# mainboard.net
KiCad netlist of a schematic drawn in EAGLE
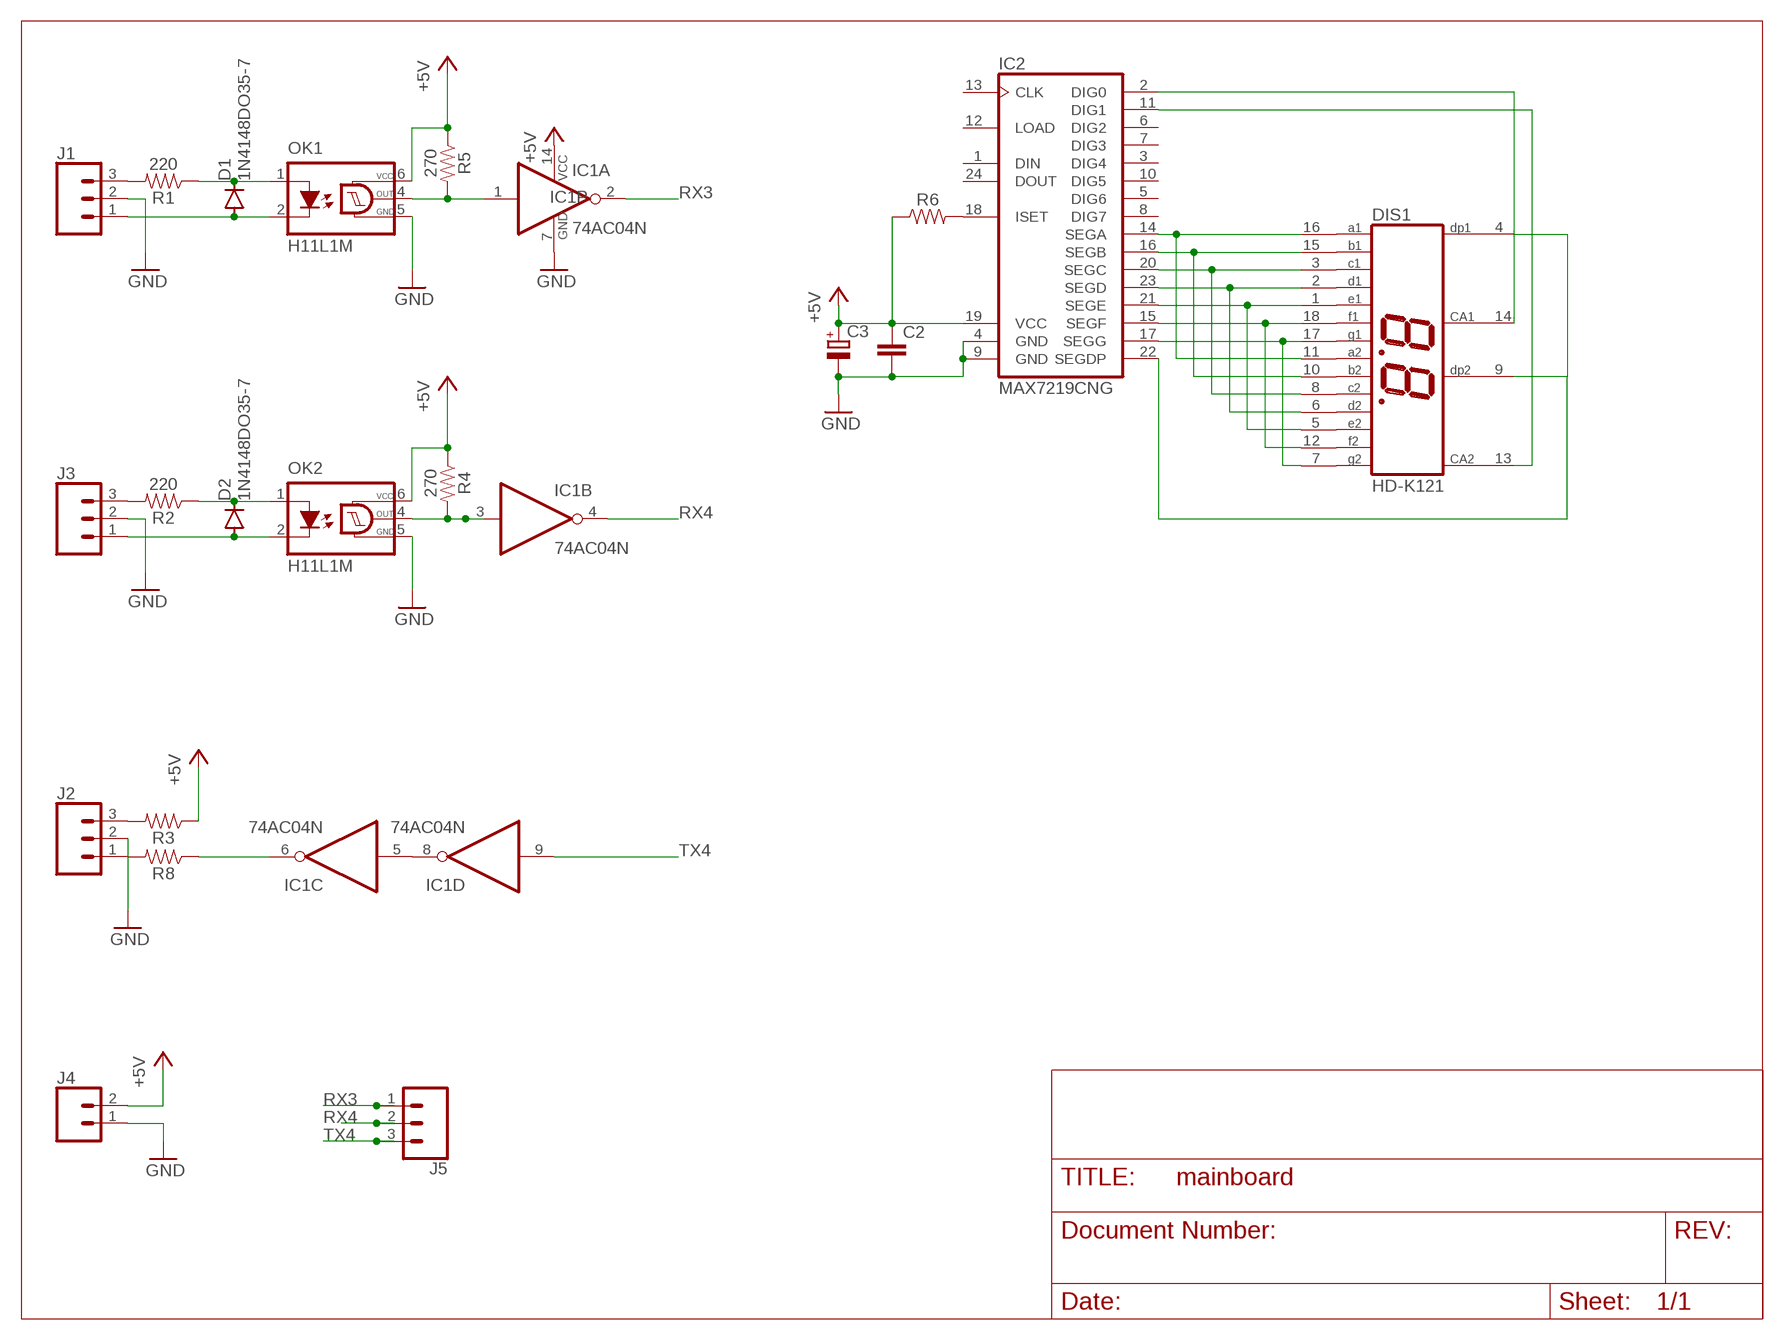
[diagram p0: schematic, sheet 1]

(export (version "E")
  (design (tool "Eeschema 10.0.6"))
  (components
    (comp (ref "C2")
      (value "C-EU025-025X050")
      (footprint "eagle-import:C025-025X050")
      (libsource (lib "eagle-import") (part "C-EU025-025X050"))
    )
    (comp (ref "C3")
      (value "CPOL-EUE1.8-4")
      (footprint "eagle-import:E1,8-4")
      (libsource (lib "eagle-import") (part "CPOL-EUE1.8-4"))
    )
    (comp (ref "D1")
      (value "1N4148DO35-7")
      (footprint "eagle-import:DO35-7")
      (libsource (lib "eagle-import") (part "1N4148DO35-7"))
    )
    (comp (ref "D2")
      (value "1N4148DO35-7")
      (footprint "eagle-import:DO35-7")
      (libsource (lib "eagle-import") (part "1N4148DO35-7"))
    )
    (comp (ref "DIS1")
      (value "HD-K121")
      (footprint "eagle-import:HDSP-R")
      (libsource (lib "eagle-import") (part "HD-K121"))
    )
    (comp (ref "IC1")
      (value "74AC04N")
      (footprint "eagle-import:DIL14")
      (libsource (lib "eagle-import") (part "7404NAC"))
    )
    (comp (ref "IC2")
      (value "MAX7219CNG")
      (footprint "eagle-import:DIL24-3")
      (fields (field (name "MF") "MAXIM"))
      (libsource (lib "eagle-import") (part "MAX7219CNG"))
    )
    (comp (ref "J1")
      (value "CONN_03")
      (footprint "eagle-import:1X03")
      (libsource (lib "eagle-import") (part "CONN_03"))
    )
    (comp (ref "J2")
      (value "CONN_03")
      (footprint "eagle-import:1X03")
      (libsource (lib "eagle-import") (part "CONN_03"))
    )
    (comp (ref "J3")
      (value "CONN_03")
      (footprint "eagle-import:1X03")
      (libsource (lib "eagle-import") (part "CONN_03"))
    )
    (comp (ref "J4")
      (value "CONN_02")
      (footprint "eagle-import:1X02")
      (libsource (lib "eagle-import") (part "CONN_02"))
    )
    (comp (ref "J5")
      (value "CONN_03")
      (footprint "eagle-import:1X03")
      (libsource (lib "eagle-import") (part "CONN_03"))
    )
    (comp (ref "OK1")
      (value "H11L1M")
      (footprint "eagle-import:DIL06")
      (fields (field (name "MF") "FAIRCHILD SEMICONDUCTOR") (field (name "MPN") "H11L1-M"))
      (libsource (lib "eagle-import") (part "H11LM1"))
    )
    (comp (ref "OK2")
      (value "H11L1M")
      (footprint "eagle-import:DIL06")
      (fields (field (name "MF") "FAIRCHILD SEMICONDUCTOR") (field (name "MPN") "H11L1-M"))
      (libsource (lib "eagle-import") (part "H11LM1"))
    )
    (comp (ref "R1")
      (value "220")
      (footprint "eagle-import:AXIAL-0.3")
      (libsource (lib "eagle-import") (part "RESISTORAXIAL-0.3"))
    )
    (comp (ref "R2")
      (value "220")
      (footprint "eagle-import:AXIAL-0.3")
      (libsource (lib "eagle-import") (part "RESISTORAXIAL-0.3"))
    )
    (comp (ref "R3")
      (value "RESISTORAXIAL-0.3")
      (footprint "eagle-import:AXIAL-0.3")
      (libsource (lib "eagle-import") (part "RESISTORAXIAL-0.3"))
    )
    (comp (ref "R4")
      (value "270")
      (footprint "eagle-import:AXIAL-0.3")
      (libsource (lib "eagle-import") (part "RESISTORAXIAL-0.3"))
    )
    (comp (ref "R5")
      (value "270")
      (footprint "eagle-import:AXIAL-0.3")
      (libsource (lib "eagle-import") (part "RESISTORAXIAL-0.3"))
    )
    (comp (ref "R6")
      (value "RESISTORAXIAL-0.3")
      (footprint "eagle-import:AXIAL-0.3")
      (libsource (lib "eagle-import") (part "RESISTORAXIAL-0.3"))
    )
    (comp (ref "R8")
      (value "RESISTORAXIAL-0.3")
      (footprint "eagle-import:AXIAL-0.3")
      (libsource (lib "eagle-import") (part "RESISTORAXIAL-0.3"))
    )
  )
  (nets
    (net (code "1") (name "+5V") (class "Default")
      (node (ref "C2") (pin "1") (pinfunction "1_1") (pintype "passive"))
      (node (ref "C3") (pin "+") (pinfunction "+_+") (pintype "passive"))
      (node (ref "IC1") (pin "14") (pinfunction "VCC_14") (pintype "power_in"))
      (node (ref "IC2") (pin "19") (pinfunction "VCC_19") (pintype "power_in"))
      (node (ref "J4") (pin "2") (pinfunction "2_2") (pintype "passive"))
      (node (ref "OK1") (pin "6") (pinfunction "VCC_6") (pintype "power_in"))
      (node (ref "OK2") (pin "6") (pinfunction "VCC_6") (pintype "power_in"))
      (node (ref "R3") (pin "P$1") (pinfunction "1_P$1") (pintype "passive"))
      (node (ref "R4") (pin "P$1") (pinfunction "1_P$1") (pintype "passive"))
      (node (ref "R5") (pin "P$1") (pinfunction "1_P$1") (pintype "passive"))
      (node (ref "R6") (pin "P$1") (pinfunction "1_P$1") (pintype "passive"))
    )
    (net (code "2") (name "/RX3") (class "Default")
      (node (ref "IC1") (pin "2") (pinfunction "O_2") (pintype "output"))
      (node (ref "J5") (pin "1") (pinfunction "1_1") (pintype "passive"))
    )
    (net (code "3") (name "/RX4") (class "Default")
      (node (ref "IC1") (pin "4") (pinfunction "O_4") (pintype "output"))
      (node (ref "J5") (pin "2") (pinfunction "2_2") (pintype "passive"))
    )
    (net (code "4") (name "/TX4") (class "Default")
      (node (ref "IC1") (pin "9") (pinfunction "I_9") (pintype "input"))
      (node (ref "J5") (pin "3") (pinfunction "3_3") (pintype "passive"))
    )
    (net (code "5") (name "GND") (class "Default")
      (node (ref "C2") (pin "2") (pinfunction "2_2") (pintype "passive"))
      (node (ref "C3") (pin "-") (pinfunction "-_-") (pintype "passive"))
      (node (ref "IC1") (pin "7") (pinfunction "GND_7") (pintype "power_in"))
      (node (ref "IC2") (pin "4") (pinfunction "GND_4") (pintype "power_in"))
      (node (ref "IC2") (pin "9") (pinfunction "GND_9") (pintype "power_in"))
      (node (ref "J1") (pin "2") (pinfunction "2_2") (pintype "passive"))
      (node (ref "J2") (pin "2") (pinfunction "2_2") (pintype "passive"))
      (node (ref "J3") (pin "2") (pinfunction "2_2") (pintype "passive"))
      (node (ref "J4") (pin "1") (pinfunction "1_1") (pintype "passive"))
      (node (ref "OK1") (pin "5") (pinfunction "GND_5") (pintype "power_in"))
      (node (ref "OK2") (pin "5") (pinfunction "GND_5") (pintype "power_in"))
    )
    (net (code "6") (name "Net-(DIS1-A1)") (class "Default")
      (node (ref "DIS1") (pin "11") (pinfunction "A2_11") (pintype "passive"))
      (node (ref "DIS1") (pin "16") (pinfunction "A1_16") (pintype "passive"))
      (node (ref "IC2") (pin "14") (pinfunction "SEGA_14") (pintype "output"))
    )
    (net (code "7") (name "Net-(DIS1-B1)") (class "Default")
      (node (ref "DIS1") (pin "10") (pinfunction "B2_10") (pintype "passive"))
      (node (ref "DIS1") (pin "15") (pinfunction "B1_15") (pintype "passive"))
      (node (ref "IC2") (pin "16") (pinfunction "SEGB_16") (pintype "output"))
    )
    (net (code "8") (name "Net-(DIS1-C1)") (class "Default")
      (node (ref "DIS1") (pin "3") (pinfunction "C1_3") (pintype "passive"))
      (node (ref "DIS1") (pin "8") (pinfunction "C2_8") (pintype "passive"))
      (node (ref "IC2") (pin "20") (pinfunction "SEGC_20") (pintype "output"))
    )
    (net (code "9") (name "Net-(DIS1-CA1)") (class "Default")
      (node (ref "DIS1") (pin "14") (pinfunction "CA1_14") (pintype "passive"))
      (node (ref "IC2") (pin "2") (pinfunction "DIG0_2") (pintype "output"))
    )
    (net (code "10") (name "Net-(DIS1-CA2)") (class "Default")
      (node (ref "DIS1") (pin "13") (pinfunction "CA2_13") (pintype "passive"))
      (node (ref "IC2") (pin "11") (pinfunction "DIG1_11") (pintype "output"))
    )
    (net (code "11") (name "Net-(DIS1-D1)") (class "Default")
      (node (ref "DIS1") (pin "2") (pinfunction "D1_2") (pintype "passive"))
      (node (ref "DIS1") (pin "6") (pinfunction "D2_6") (pintype "passive"))
      (node (ref "IC2") (pin "23") (pinfunction "SEGD_23") (pintype "output"))
    )
    (net (code "12") (name "Net-(DIS1-DP1)") (class "Default")
      (node (ref "DIS1") (pin "4") (pinfunction "DP1_4") (pintype "passive"))
      (node (ref "DIS1") (pin "9") (pinfunction "DP2_9") (pintype "passive"))
      (node (ref "IC2") (pin "22") (pinfunction "SEGDP_22") (pintype "output"))
    )
    (net (code "13") (name "Net-(DIS1-E1)") (class "Default")
      (node (ref "DIS1") (pin "1") (pinfunction "E1_1") (pintype "passive"))
      (node (ref "DIS1") (pin "5") (pinfunction "E2_5") (pintype "passive"))
      (node (ref "IC2") (pin "21") (pinfunction "SEGE_21") (pintype "output"))
    )
    (net (code "14") (name "Net-(DIS1-F1)") (class "Default")
      (node (ref "DIS1") (pin "12") (pinfunction "F2_12") (pintype "passive"))
      (node (ref "DIS1") (pin "18") (pinfunction "F1_18") (pintype "passive"))
      (node (ref "IC2") (pin "15") (pinfunction "SEGF_15") (pintype "output"))
    )
    (net (code "15") (name "Net-(DIS1-G1)") (class "Default")
      (node (ref "DIS1") (pin "17") (pinfunction "G1_17") (pintype "passive"))
      (node (ref "DIS1") (pin "7") (pinfunction "G2_7") (pintype "passive"))
      (node (ref "IC2") (pin "17") (pinfunction "SEGG_17") (pintype "output"))
    )
    (net (code "16") (name "Net-(IC1A-I)") (class "Default")
      (node (ref "IC1") (pin "1") (pinfunction "I_1") (pintype "input"))
      (node (ref "OK1") (pin "4") (pinfunction "OUT_4") (pintype "output"))
      (node (ref "R5") (pin "P$2") (pinfunction "2_P$2") (pintype "passive"))
    )
    (net (code "17") (name "Net-(IC1B-I)") (class "Default")
      (node (ref "IC1") (pin "3") (pinfunction "I_3") (pintype "input"))
      (node (ref "OK2") (pin "4") (pinfunction "OUT_4") (pintype "output"))
      (node (ref "R4") (pin "P$2") (pinfunction "2_P$2") (pintype "passive"))
    )
    (net (code "18") (name "Net-(IC1C-I)") (class "Default")
      (node (ref "IC1") (pin "5") (pinfunction "I_5") (pintype "input"))
      (node (ref "IC1") (pin "8") (pinfunction "O_8") (pintype "output"))
    )
    (net (code "19") (name "Net-(IC1C-O)") (class "Default")
      (node (ref "IC1") (pin "6") (pinfunction "O_6") (pintype "output"))
      (node (ref "R8") (pin "P$1") (pinfunction "1_P$1") (pintype "passive"))
    )
    (net (code "20") (name "Net-(IC2-ISET)") (class "Default")
      (node (ref "IC2") (pin "18") (pinfunction "ISET_18") (pintype "input"))
      (node (ref "R6") (pin "P$2") (pinfunction "2_P$2") (pintype "passive"))
    )
    (net (code "21") (name "Net-(OK1-A)") (class "Default")
      (node (ref "D1") (pin "C") (pinfunction "C_C") (pintype "passive"))
      (node (ref "OK1") (pin "1") (pinfunction "A_1") (pintype "passive"))
      (node (ref "R1") (pin "P$1") (pinfunction "1_P$1") (pintype "passive"))
    )
    (net (code "22") (name "Net-(OK1-C)") (class "Default")
      (node (ref "D1") (pin "A") (pinfunction "A_A") (pintype "passive"))
      (node (ref "J1") (pin "1") (pinfunction "1_1") (pintype "passive"))
      (node (ref "OK1") (pin "2") (pinfunction "C_2") (pintype "passive"))
    )
    (net (code "23") (name "Net-(OK2-A)") (class "Default")
      (node (ref "D2") (pin "C") (pinfunction "C_C") (pintype "passive"))
      (node (ref "OK2") (pin "1") (pinfunction "A_1") (pintype "passive"))
      (node (ref "R2") (pin "P$1") (pinfunction "1_P$1") (pintype "passive"))
    )
    (net (code "24") (name "Net-(OK2-C)") (class "Default")
      (node (ref "D2") (pin "A") (pinfunction "A_A") (pintype "passive"))
      (node (ref "J3") (pin "1") (pinfunction "1_1") (pintype "passive"))
      (node (ref "OK2") (pin "2") (pinfunction "C_2") (pintype "passive"))
    )
    (net (code "25") (name "Net-(R1-2)") (class "Default")
      (node (ref "J1") (pin "3") (pinfunction "3_3") (pintype "passive"))
      (node (ref "R1") (pin "P$2") (pinfunction "2_P$2") (pintype "passive"))
    )
    (net (code "26") (name "Net-(R2-2)") (class "Default")
      (node (ref "J3") (pin "3") (pinfunction "3_3") (pintype "passive"))
      (node (ref "R2") (pin "P$2") (pinfunction "2_P$2") (pintype "passive"))
    )
    (net (code "27") (name "Net-(R3-2)") (class "Default")
      (node (ref "J2") (pin "3") (pinfunction "3_3") (pintype "passive"))
      (node (ref "R3") (pin "P$2") (pinfunction "2_P$2") (pintype "passive"))
    )
    (net (code "28") (name "Net-(R8-2)") (class "Default")
      (node (ref "J2") (pin "1") (pinfunction "1_1") (pintype "passive"))
      (node (ref "R8") (pin "P$2") (pinfunction "2_P$2") (pintype "passive"))
    )
    (net (code "29") (name "unconnected-(IC2-CLK-Pad13)") (class "Default")
      (node (ref "IC2") (pin "13") (pinfunction "CLK_13") (pintype "input"))
    )
    (net (code "30") (name "unconnected-(IC2-DIG2-Pad6)") (class "Default")
      (node (ref "IC2") (pin "6") (pinfunction "DIG2_6") (pintype "output"))
    )
    (net (code "31") (name "unconnected-(IC2-DIG3-Pad7)") (class "Default")
      (node (ref "IC2") (pin "7") (pinfunction "DIG3_7") (pintype "output"))
    )
    (net (code "32") (name "unconnected-(IC2-DIG4-Pad3)") (class "Default")
      (node (ref "IC2") (pin "3") (pinfunction "DIG4_3") (pintype "output"))
    )
    (net (code "33") (name "unconnected-(IC2-DIG5-Pad10)") (class "Default")
      (node (ref "IC2") (pin "10") (pinfunction "DIG5_10") (pintype "output"))
    )
    (net (code "34") (name "unconnected-(IC2-DIG6-Pad5)") (class "Default")
      (node (ref "IC2") (pin "5") (pinfunction "DIG6_5") (pintype "output"))
    )
    (net (code "35") (name "unconnected-(IC2-DIG7-Pad8)") (class "Default")
      (node (ref "IC2") (pin "8") (pinfunction "DIG7_8") (pintype "output"))
    )
    (net (code "36") (name "unconnected-(IC2-DIN-Pad1)") (class "Default")
      (node (ref "IC2") (pin "1") (pinfunction "DIN_1") (pintype "input"))
    )
    (net (code "37") (name "unconnected-(IC2-DOUT-Pad24)") (class "Default")
      (node (ref "IC2") (pin "24") (pinfunction "DOUT_24") (pintype "output"))
    )
    (net (code "38") (name "unconnected-(IC2-LOAD-Pad12)") (class "Default")
      (node (ref "IC2") (pin "12") (pinfunction "LOAD_12") (pintype "input"))
    )
  )
)
